# Power.net
KiCad netlist of a schematic drawn in Altium Designer
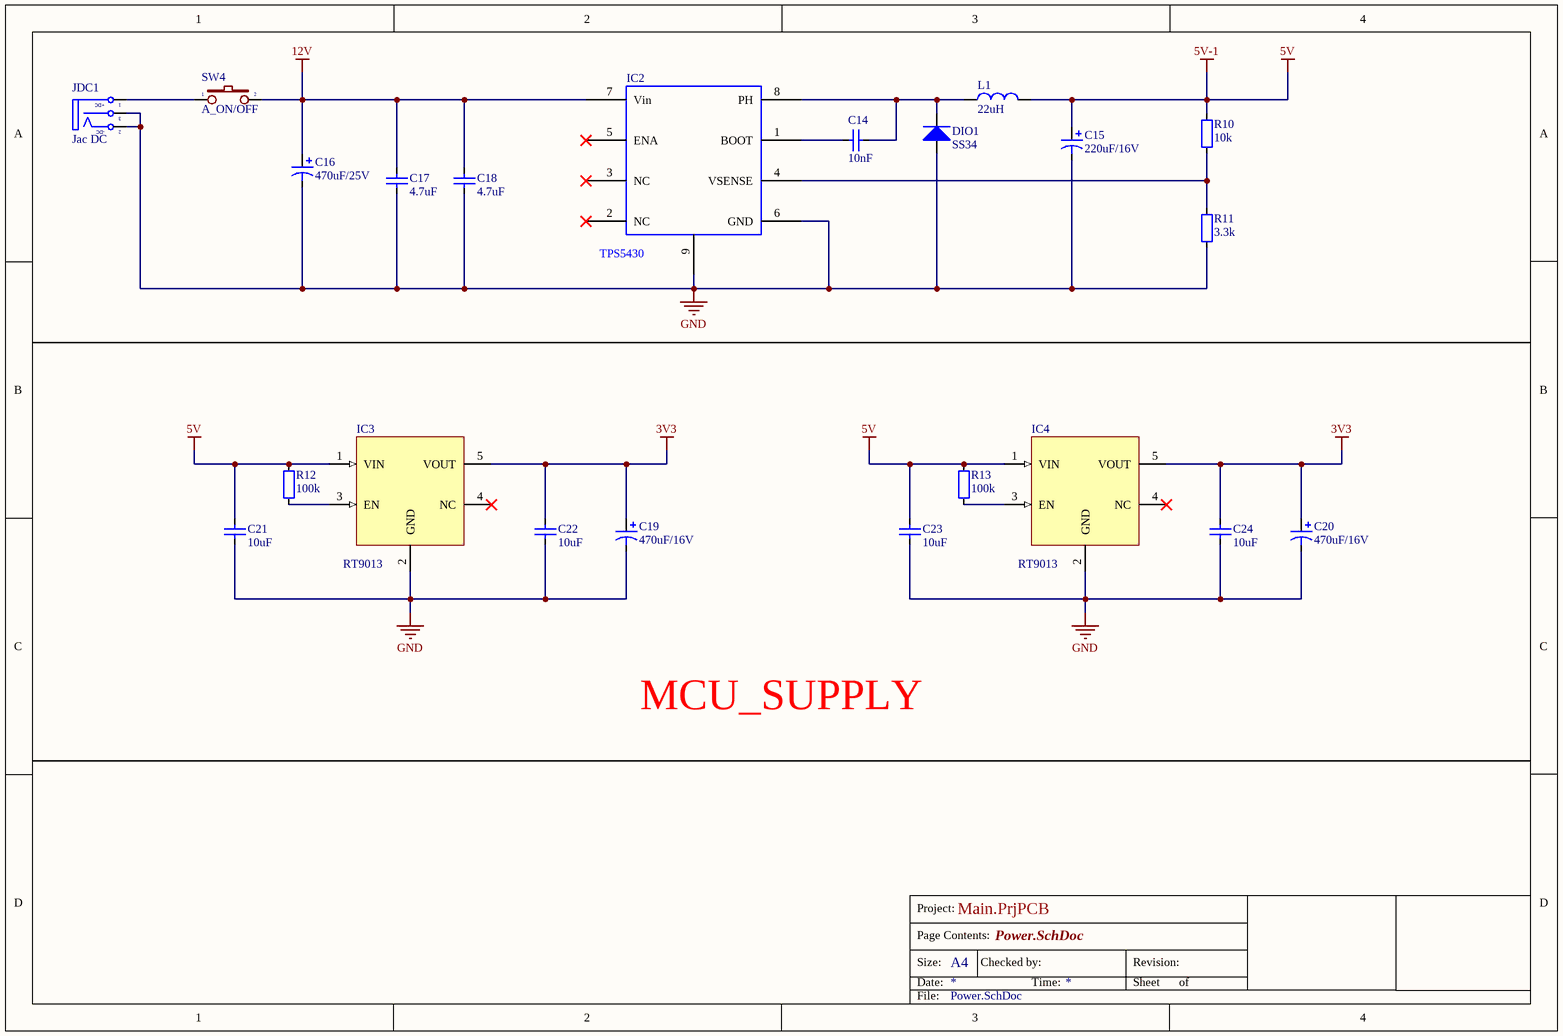
[diagram p0: Power.SchDoc]

(export (version "E")
  (design (tool "Eeschema 10.0.6"))
  (components
    (comp (ref "C14")
      (value "10nF")
      (footprint "CAP_0805")
      (description "Capacitor")
      (fields (field (name "PUBLISHER") "Altium Limited"))
      (libsource (lib "My Library") (part "CapSMD"))
    )
    (comp (ref "C15")
      (value "220uF/16V")
      (footprint "C8mm")
      (description "Polarized Capacitor (Axial)")
      (fields (field (name "PUBLISHER") "Altium Limited"))
      (libsource (lib "My Library") (part "Cap Pol"))
    )
    (comp (ref "C16")
      (value "470uF/25V")
      (footprint "C8mm")
      (description "Polarized Capacitor (Axial)")
      (fields (field (name "PUBLISHER") "Altium Limited"))
      (libsource (lib "My Library") (part "Cap Pol"))
    )
    (comp (ref "C17")
      (value "4.7uF")
      (footprint "CAP_0805")
      (description "Capacitor")
      (fields (field (name "PUBLISHER") "Altium Limited"))
      (libsource (lib "My Library") (part "CapSMD"))
    )
    (comp (ref "C18")
      (value "4.7uF")
      (footprint "CAP_0805")
      (description "Capacitor")
      (fields (field (name "PUBLISHER") "Altium Limited"))
      (libsource (lib "My Library") (part "CapSMD"))
    )
    (comp (ref "C19")
      (value "470uF/16V")
      (footprint "C8mm")
      (description "Polarized Capacitor (Axial)")
      (fields (field (name "PUBLISHER") "Altium Limited"))
      (libsource (lib "My Library") (part "Cap Pol"))
    )
    (comp (ref "C20")
      (value "470uF/16V")
      (footprint "C8mm")
      (description "Polarized Capacitor (Axial)")
      (fields (field (name "PUBLISHER") "Altium Limited"))
      (libsource (lib "My Library") (part "Cap Pol"))
    )
    (comp (ref "C21")
      (value "10uF")
      (footprint "CAP_0805")
      (description "Capacitor")
      (fields (field (name "PUBLISHER") "Altium Limited"))
      (libsource (lib "My Library") (part "CapSMD"))
    )
    (comp (ref "C22")
      (value "10uF")
      (footprint "CAP_0805")
      (description "Capacitor")
      (fields (field (name "PUBLISHER") "Altium Limited"))
      (libsource (lib "My Library") (part "CapSMD"))
    )
    (comp (ref "C23")
      (value "10uF")
      (footprint "CAP_0805")
      (description "Capacitor")
      (fields (field (name "PUBLISHER") "Altium Limited"))
      (libsource (lib "My Library") (part "CapSMD"))
    )
    (comp (ref "C24")
      (value "10uF")
      (footprint "CAP_0805")
      (description "Capacitor")
      (fields (field (name "PUBLISHER") "Altium Limited"))
      (libsource (lib "My Library") (part "CapSMD"))
    )
    (comp (ref "DIO1")
      (value "SS34")
      (footprint "DIO-SMD-106")
      (description "Default Diode")
      (fields (field (name "PUBLISHER") "Altium Limited"))
      (libsource (lib "Ven_lib") (part "Diode SMD"))
    )
    (comp (ref "IC2")
      (value "TPS5430")
      (footprint "TPS5430-2")
      (fields (field (name "NAME") "TPS5430"))
      (libsource (lib "My Library") (part "TPS5430"))
    )
    (comp (ref "IC3")
      (value "RT9013")
      (footprint "SOT23-5")
      (description "RT9013-33GB IC REG LINEAR 3.3V 500mA SOT23-5")
      (libsource (lib "My Library") (part "RT9013"))
    )
    (comp (ref "IC4")
      (value "RT9013")
      (footprint "SOT23-5")
      (description "RT9013-33GB IC REG LINEAR 3.3V 500mA SOT23-5")
      (libsource (lib "My Library") (part "RT9013"))
    )
    (comp (ref "JDC1")
      (value "Jac DC")
      (footprint "DC-IN")
      (description "Jac DC input")
      (libsource (lib "My Library") (part "DCIN"))
    )
    (comp (ref "L1")
      (value "22uH")
      (footprint "L-SMD-M-7.3x4.5")
      (description "Inductor")
      (libsource (lib "My Library") (part "Inductor"))
    )
    (comp (ref "R10")
      (value "10k")
      (footprint "RES-SMD-0805")
      (description "Resistor")
      (fields
        (field (name "MANUFACTURER") "Generic Components")
        (field (name "PUBLISHER") "Altium Hobart Technology Centre")
      )
      (libsource (lib "My Library") (part "Resistor - SMD"))
    )
    (comp (ref "R11")
      (value "3.3k")
      (footprint "RES-SMD-0805")
      (description "Resistor")
      (fields
        (field (name "MANUFACTURER") "Generic Components")
        (field (name "PUBLISHER") "Altium Hobart Technology Centre")
      )
      (libsource (lib "My Library") (part "Resistor - SMD"))
    )
    (comp (ref "R12")
      (value "100k")
      (footprint "RES-SMD-0805")
      (description "Resistor")
      (fields
        (field (name "MANUFACTURER") "Generic Components")
        (field (name "PUBLISHER") "Altium Hobart Technology Centre")
      )
      (libsource (lib "My Library") (part "Resistor - SMD"))
    )
    (comp (ref "R13")
      (value "100k")
      (footprint "RES-SMD-0805")
      (description "Resistor")
      (fields
        (field (name "MANUFACTURER") "Generic Components")
        (field (name "PUBLISHER") "Altium Hobart Technology Centre")
      )
      (libsource (lib "My Library") (part "Resistor - SMD"))
    )
    (comp (ref "SW4")
      (value "A_ON/OFF")
      (footprint "SW2")
      (description "Switch button 2 pin")
      (libsource (lib "My Library") (part "SW2"))
    )
  )
  (nets
    (net (code "1") (name "3V3") (class "Default")
      (node (ref "C19") (pin "1") (pinfunction "1_1") (pintype "passive"))
      (node (ref "C20") (pin "1") (pinfunction "1_1") (pintype "passive"))
      (node (ref "C22") (pin "2") (pinfunction "2_2") (pintype "passive"))
      (node (ref "C24") (pin "2") (pinfunction "2_2") (pintype "passive"))
      (node (ref "IC3") (pin "5") (pinfunction "VOUT_5") (pintype "power_in"))
      (node (ref "IC4") (pin "5") (pinfunction "VOUT_5") (pintype "power_in"))
    )
    (net (code "2") (name "5V") (class "Default")
      (node (ref "C15") (pin "1") (pinfunction "1_1") (pintype "passive"))
      (node (ref "C21") (pin "2") (pinfunction "2_2") (pintype "passive"))
      (node (ref "C23") (pin "2") (pinfunction "2_2") (pintype "passive"))
      (node (ref "IC3") (pin "1") (pinfunction "VIN_1") (pintype "input"))
      (node (ref "IC4") (pin "1") (pinfunction "VIN_1") (pintype "input"))
      (node (ref "L1") (pin "2") (pinfunction "2_2") (pintype "passive"))
      (node (ref "R10") (pin "2") (pinfunction "2_2") (pintype "passive"))
      (node (ref "R12") (pin "1") (pinfunction "1_1") (pintype "passive"))
      (node (ref "R13") (pin "1") (pinfunction "1_1") (pintype "passive"))
    )
    (net (code "3") (name "12V") (class "Default")
      (node (ref "C16") (pin "1") (pinfunction "1_1") (pintype "passive"))
      (node (ref "C17") (pin "2") (pinfunction "2_2") (pintype "passive"))
      (node (ref "C18") (pin "2") (pinfunction "2_2") (pintype "passive"))
      (node (ref "IC2") (pin "7") (pinfunction "Vin_7") (pintype "passive"))
      (node (ref "SW4") (pin "2") (pinfunction "2_2") (pintype "passive"))
    )
    (net (code "4") (name "GND") (class "Default")
      (node (ref "C15") (pin "2") (pinfunction "2_2") (pintype "passive"))
      (node (ref "C16") (pin "2") (pinfunction "2_2") (pintype "passive"))
      (node (ref "C17") (pin "1") (pinfunction "1_1") (pintype "passive"))
      (node (ref "C18") (pin "1") (pinfunction "1_1") (pintype "passive"))
      (node (ref "C19") (pin "2") (pinfunction "2_2") (pintype "passive"))
      (node (ref "C20") (pin "2") (pinfunction "2_2") (pintype "passive"))
      (node (ref "C21") (pin "1") (pinfunction "1_1") (pintype "passive"))
      (node (ref "C22") (pin "1") (pinfunction "1_1") (pintype "passive"))
      (node (ref "C23") (pin "1") (pinfunction "1_1") (pintype "passive"))
      (node (ref "C24") (pin "1") (pinfunction "1_1") (pintype "passive"))
      (node (ref "DIO1") (pin "1") (pinfunction "A_1") (pintype "passive"))
      (node (ref "IC2") (pin "6") (pinfunction "GND_6") (pintype "passive"))
      (node (ref "IC2") (pin "9") (pinfunction "PWR_PAD_9") (pintype "passive"))
      (node (ref "IC3") (pin "2") (pinfunction "GND_2") (pintype "passive"))
      (node (ref "IC4") (pin "2") (pinfunction "GND_2") (pintype "passive"))
      (node (ref "JDC1") (pin "2") (pinfunction "TN_2") (pintype "passive"))
      (node (ref "JDC1") (pin "3") (pinfunction "S_3") (pintype "power_in"))
      (node (ref "R11") (pin "1") (pinfunction "1_1") (pintype "passive"))
    )
    (net (code "5") (name "Net-(DIO1-K)") (class "Default")
      (node (ref "C14") (pin "1") (pinfunction "1_1") (pintype "passive"))
      (node (ref "DIO1") (pin "2") (pinfunction "K_2") (pintype "passive"))
      (node (ref "IC2") (pin "8") (pinfunction "PH_8") (pintype "passive"))
      (node (ref "L1") (pin "1") (pinfunction "1_1") (pintype "passive"))
    )
    (net (code "6") (name "Net-(IC2-BOOT)") (class "Default")
      (node (ref "C14") (pin "2") (pinfunction "2_2") (pintype "passive"))
      (node (ref "IC2") (pin "1") (pinfunction "BOOT_1") (pintype "passive"))
    )
    (net (code "7") (name "Net-(IC2-VSENSE)") (class "Default")
      (node (ref "IC2") (pin "4") (pinfunction "VSENSE_4") (pintype "passive"))
      (node (ref "R10") (pin "1") (pinfunction "1_1") (pintype "passive"))
      (node (ref "R11") (pin "2") (pinfunction "2_2") (pintype "passive"))
    )
    (net (code "8") (name "Net-(IC3-EN)") (class "Default")
      (node (ref "IC3") (pin "3") (pinfunction "EN_3") (pintype "input"))
      (node (ref "R12") (pin "2") (pinfunction "2_2") (pintype "passive"))
    )
    (net (code "9") (name "Net-(IC4-EN)") (class "Default")
      (node (ref "IC4") (pin "3") (pinfunction "EN_3") (pintype "input"))
      (node (ref "R13") (pin "2") (pinfunction "2_2") (pintype "passive"))
    )
    (net (code "10") (name "Net-(JDC1-T)") (class "Default")
      (node (ref "JDC1") (pin "1") (pinfunction "T_1") (pintype "passive"))
      (node (ref "SW4") (pin "1") (pinfunction "1_1") (pintype "passive"))
    )
    (net (code "11") (name "unconnected-(IC2-ENA-Pad5)") (class "Default")
      (node (ref "IC2") (pin "5") (pinfunction "ENA_5") (pintype "passive+no_connect"))
    )
    (net (code "12") (name "unconnected-(IC2-NC-Pad2)") (class "Default")
      (node (ref "IC2") (pin "2") (pinfunction "NC_2") (pintype "passive+no_connect"))
    )
    (net (code "13") (name "unconnected-(IC2-NC-Pad3)") (class "Default")
      (node (ref "IC2") (pin "3") (pinfunction "NC_3") (pintype "passive+no_connect"))
    )
    (net (code "14") (name "unconnected-(IC3-NC-Pad4)") (class "Default")
      (node (ref "IC3") (pin "4") (pinfunction "NC_4") (pintype "passive+no_connect"))
    )
    (net (code "15") (name "unconnected-(IC4-NC-Pad4)") (class "Default")
      (node (ref "IC4") (pin "4") (pinfunction "NC_4") (pintype "passive+no_connect"))
    )
  )
)
